# AVRPowerSupply.net
KiCad netlist of a schematic drawn in EAGLE
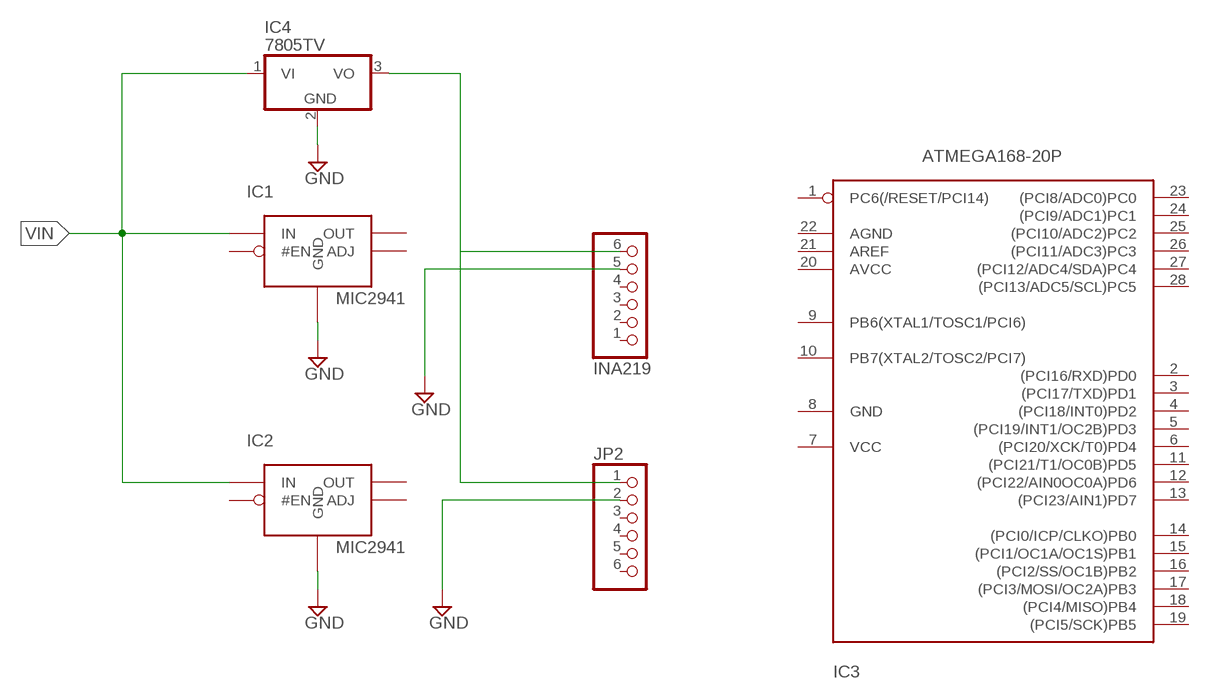
[diagram p0: schematic, sheet 1]

(export (version "E")
  (design (tool "Eeschema 10.0.6"))
  (components
    (comp (ref "IC1")
      (value "BBSUP_MIC2941")
      (footprint "eagle-import:BBSUP_TO220-5")
      (libsource (lib "eagle-import") (part "BBSUP_MIC2941"))
    )
    (comp (ref "IC2")
      (value "BBSUP_MIC2941")
      (footprint "eagle-import:BBSUP_TO220-5")
      (libsource (lib "eagle-import") (part "BBSUP_MIC2941"))
    )
    (comp (ref "IC3")
      (value "ATMEGA168-20P")
      (footprint "eagle-import:DIL28-3")
      (libsource (lib "eagle-import") (part "ATMEGA168P-20"))
    )
    (comp (ref "IC4")
      (value "7805TV")
      (footprint "eagle-import:TO220V")
      (libsource (lib "eagle-import") (part "78TV05"))
    )
    (comp (ref "INA219")
      (value "PINHD-1X6")
      (footprint "eagle-import:1X06")
      (libsource (lib "eagle-import") (part "PINHD-1X6"))
    )
    (comp (ref "JP2")
      (value "PINHD-1X6")
      (footprint "eagle-import:1X06")
      (libsource (lib "eagle-import") (part "PINHD-1X6"))
    )
  )
  (nets
    (net (code "1") (name "GND") (class "Default")
      (node (ref "IC1") (pin "3") (pinfunction "GND_3") (pintype "input"))
      (node (ref "IC2") (pin "3") (pinfunction "GND_3") (pintype "input"))
      (node (ref "IC4") (pin "2") (pinfunction "GND_2") (pintype "passive"))
      (node (ref "INA219") (pin "5") (pinfunction "5_5") (pintype "passive"))
      (node (ref "JP2") (pin "2") (pinfunction "2_2") (pintype "passive"))
    )
    (net (code "2") (name "Net-(IC4-VO)") (class "Default")
      (node (ref "IC4") (pin "3") (pinfunction "VO_3") (pintype "passive"))
      (node (ref "INA219") (pin "6") (pinfunction "6_6") (pintype "passive"))
      (node (ref "JP2") (pin "1") (pinfunction "1_1") (pintype "passive"))
    )
    (net (code "3") (name "VIN") (class "Default")
      (node (ref "IC1") (pin "4") (pinfunction "IN_4") (pintype "input"))
      (node (ref "IC2") (pin "4") (pinfunction "IN_4") (pintype "input"))
      (node (ref "IC4") (pin "1") (pinfunction "VI_1") (pintype "input"))
    )
    (net (code "4") (name "unconnected-(IC1-#EN-Pad2)") (class "Default")
      (node (ref "IC1") (pin "2") (pinfunction "#EN_2") (pintype "input"))
    )
    (net (code "5") (name "unconnected-(IC1-ADJ-Pad1)") (class "Default")
      (node (ref "IC1") (pin "1") (pinfunction "ADJ_1") (pintype "input"))
    )
    (net (code "6") (name "unconnected-(IC1-OUT-Pad5)") (class "Default")
      (node (ref "IC1") (pin "5") (pinfunction "OUT_5") (pintype "passive"))
    )
    (net (code "7") (name "unconnected-(IC2-#EN-Pad2)") (class "Default")
      (node (ref "IC2") (pin "2") (pinfunction "#EN_2") (pintype "input"))
    )
    (net (code "8") (name "unconnected-(IC2-ADJ-Pad1)") (class "Default")
      (node (ref "IC2") (pin "1") (pinfunction "ADJ_1") (pintype "input"))
    )
    (net (code "9") (name "unconnected-(IC2-OUT-Pad5)") (class "Default")
      (node (ref "IC2") (pin "5") (pinfunction "OUT_5") (pintype "passive"))
    )
    (net (code "10") (name "unconnected-(IC3-(PCI0{slash}ICP{slash}CLKO)PB0-Pad14)") (class "Default")
      (node (ref "IC3") (pin "14") (pinfunction "(PCI0/ICP/CLKO)PB0_14") (pintype "bidirectional"))
    )
    (net (code "11") (name "unconnected-(IC3-(PCI1{slash}OC1A{slash}OC1S)PB1-Pad15)") (class "Default")
      (node (ref "IC3") (pin "15") (pinfunction "(PCI1/OC1A/OC1S)PB1_15") (pintype "bidirectional"))
    )
    (net (code "12") (name "unconnected-(IC3-(PCI2{slash}SS{slash}OC1B)PB2-Pad16)") (class "Default")
      (node (ref "IC3") (pin "16") (pinfunction "(PCI2/SS/OC1B)PB2_16") (pintype "bidirectional"))
    )
    (net (code "13") (name "unconnected-(IC3-(PCI3{slash}MOSI{slash}OC2A)PB3-Pad17)") (class "Default")
      (node (ref "IC3") (pin "17") (pinfunction "(PCI3/MOSI/OC2A)PB3_17") (pintype "bidirectional"))
    )
    (net (code "14") (name "unconnected-(IC3-(PCI4{slash}MISO)PB4-Pad18)") (class "Default")
      (node (ref "IC3") (pin "18") (pinfunction "(PCI4/MISO)PB4_18") (pintype "bidirectional"))
    )
    (net (code "15") (name "unconnected-(IC3-(PCI5{slash}SCK)PB5-Pad19)") (class "Default")
      (node (ref "IC3") (pin "19") (pinfunction "(PCI5/SCK)PB5_19") (pintype "bidirectional"))
    )
    (net (code "16") (name "unconnected-(IC3-(PCI8{slash}ADC0)PC0-Pad23)") (class "Default")
      (node (ref "IC3") (pin "23") (pinfunction "(PCI8/ADC0)PC0_23") (pintype "bidirectional"))
    )
    (net (code "17") (name "unconnected-(IC3-(PCI9{slash}ADC1)PC1-Pad24)") (class "Default")
      (node (ref "IC3") (pin "24") (pinfunction "(PCI9/ADC1)PC1_24") (pintype "bidirectional"))
    )
    (net (code "18") (name "unconnected-(IC3-(PCI10{slash}ADC2)PC2-Pad25)") (class "Default")
      (node (ref "IC3") (pin "25") (pinfunction "(PCI10/ADC2)PC2_25") (pintype "bidirectional"))
    )
    (net (code "19") (name "unconnected-(IC3-(PCI11{slash}ADC3)PC3-Pad26)") (class "Default")
      (node (ref "IC3") (pin "26") (pinfunction "(PCI11/ADC3)PC3_26") (pintype "bidirectional"))
    )
    (net (code "20") (name "unconnected-(IC3-(PCI12{slash}ADC4{slash}SDA)PC4-Pad27)") (class "Default")
      (node (ref "IC3") (pin "27") (pinfunction "(PCI12/ADC4/SDA)PC4_27") (pintype "bidirectional"))
    )
    (net (code "21") (name "unconnected-(IC3-(PCI13{slash}ADC5{slash}SCL)PC5-Pad28)") (class "Default")
      (node (ref "IC3") (pin "28") (pinfunction "(PCI13/ADC5/SCL)PC5_28") (pintype "bidirectional"))
    )
    (net (code "22") (name "unconnected-(IC3-(PCI16{slash}RXD)PD0-Pad2)") (class "Default")
      (node (ref "IC3") (pin "2") (pinfunction "(PCI16/RXD)PD0_2") (pintype "bidirectional"))
    )
    (net (code "23") (name "unconnected-(IC3-(PCI17{slash}TXD)PD1-Pad3)") (class "Default")
      (node (ref "IC3") (pin "3") (pinfunction "(PCI17/TXD)PD1_3") (pintype "bidirectional"))
    )
    (net (code "24") (name "unconnected-(IC3-(PCI18{slash}INT0)PD2-Pad4)") (class "Default")
      (node (ref "IC3") (pin "4") (pinfunction "(PCI18/INT0)PD2_4") (pintype "bidirectional"))
    )
    (net (code "25") (name "unconnected-(IC3-(PCI19{slash}INT1{slash}OC2B)PD3-Pad5)") (class "Default")
      (node (ref "IC3") (pin "5") (pinfunction "(PCI19/INT1/OC2B)PD3_5") (pintype "bidirectional"))
    )
    (net (code "26") (name "unconnected-(IC3-(PCI20{slash}XCK{slash}T0)PD4-Pad6)") (class "Default")
      (node (ref "IC3") (pin "6") (pinfunction "(PCI20/XCK/T0)PD4_6") (pintype "bidirectional"))
    )
    (net (code "27") (name "unconnected-(IC3-(PCI21{slash}T1{slash}OC0B)PD5-Pad11)") (class "Default")
      (node (ref "IC3") (pin "11") (pinfunction "(PCI21/T1/OC0B)PD5_11") (pintype "bidirectional"))
    )
    (net (code "28") (name "unconnected-(IC3-(PCI22{slash}AIN0OC0A)PD6-Pad12)") (class "Default")
      (node (ref "IC3") (pin "12") (pinfunction "(PCI22/AIN0OC0A)PD6_12") (pintype "bidirectional"))
    )
    (net (code "29") (name "unconnected-(IC3-(PCI23{slash}AIN1)PD7-Pad13)") (class "Default")
      (node (ref "IC3") (pin "13") (pinfunction "(PCI23/AIN1)PD7_13") (pintype "bidirectional"))
    )
    (net (code "30") (name "unconnected-(IC3-AGND-Pad22)") (class "Default")
      (node (ref "IC3") (pin "22") (pinfunction "AGND_22") (pintype "bidirectional"))
    )
    (net (code "31") (name "unconnected-(IC3-AREF-Pad21)") (class "Default")
      (node (ref "IC3") (pin "21") (pinfunction "AREF_21") (pintype "bidirectional"))
    )
    (net (code "32") (name "unconnected-(IC3-AVCC-Pad20)") (class "Default")
      (node (ref "IC3") (pin "20") (pinfunction "AVCC_20") (pintype "bidirectional"))
    )
    (net (code "33") (name "unconnected-(IC3-GND-Pad8)") (class "Default")
      (node (ref "IC3") (pin "8") (pinfunction "GND_8") (pintype "bidirectional"))
    )
    (net (code "34") (name "unconnected-(IC3-PB6(XTAL1{slash}TOSC1{slash}PCI6)-Pad9)") (class "Default")
      (node (ref "IC3") (pin "9") (pinfunction "PB6(XTAL1/TOSC1/PCI6)_9") (pintype "bidirectional"))
    )
    (net (code "35") (name "unconnected-(IC3-PB7(XTAL2{slash}TOSC2{slash}PCI7)-Pad10)") (class "Default")
      (node (ref "IC3") (pin "10") (pinfunction "PB7(XTAL2/TOSC2/PCI7)_10") (pintype "bidirectional"))
    )
    (net (code "36") (name "unconnected-(IC3-PC6({slash}RESET{slash}PCI14)-Pad1)") (class "Default")
      (node (ref "IC3") (pin "1") (pinfunction "PC6(/RESET/PCI14)_1") (pintype "bidirectional"))
    )
    (net (code "37") (name "unconnected-(IC3-VCC-Pad7)") (class "Default")
      (node (ref "IC3") (pin "7") (pinfunction "VCC_7") (pintype "bidirectional"))
    )
    (net (code "38") (name "unconnected-(INA219-Pad1)") (class "Default")
      (node (ref "INA219") (pin "1") (pinfunction "1_1") (pintype "passive"))
    )
    (net (code "39") (name "unconnected-(INA219-Pad2)") (class "Default")
      (node (ref "INA219") (pin "2") (pinfunction "2_2") (pintype "passive"))
    )
    (net (code "40") (name "unconnected-(INA219-Pad3)") (class "Default")
      (node (ref "INA219") (pin "3") (pinfunction "3_3") (pintype "passive"))
    )
    (net (code "41") (name "unconnected-(INA219-Pad4)") (class "Default")
      (node (ref "INA219") (pin "4") (pinfunction "4_4") (pintype "passive"))
    )
    (net (code "42") (name "unconnected-(JP2-Pad3)") (class "Default")
      (node (ref "JP2") (pin "3") (pinfunction "3_3") (pintype "passive"))
    )
    (net (code "43") (name "unconnected-(JP2-Pad4)") (class "Default")
      (node (ref "JP2") (pin "4") (pinfunction "4_4") (pintype "passive"))
    )
    (net (code "44") (name "unconnected-(JP2-Pad5)") (class "Default")
      (node (ref "JP2") (pin "5") (pinfunction "5_5") (pintype "passive"))
    )
    (net (code "45") (name "unconnected-(JP2-Pad6)") (class "Default")
      (node (ref "JP2") (pin "6") (pinfunction "6_6") (pintype "passive"))
    )
  )
)
